# Power_Supply.net
KiCad netlist of a schematic drawn in Altium Designer
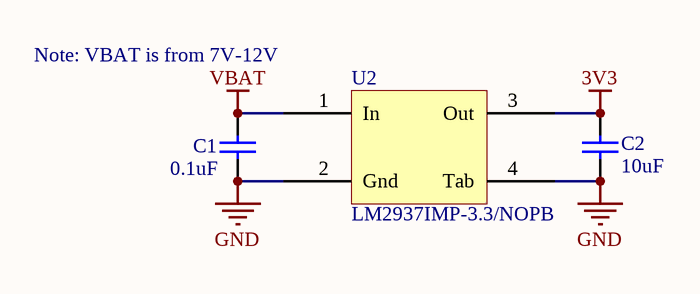
[diagram p0: Power Supply.SchDoc]

(export (version "E")
  (design (tool "Eeschema 10.0.6"))
  (components
    (comp (ref "C1")
      (value "0.1uF")
      (footprint "C1206")
      (description "Regulator Filter Cap")
      (fields (field (name "PUBLISHER") "Altium Limited"))
      (libsource (lib "Miscellaneous Devices") (part "Cap Semi"))
    )
    (comp (ref "C2")
      (value "10uF")
      (footprint "C1206")
      (description "1206 Ceramic Capacitor")
      (fields (field (name "PUBLISHER") "Altium Limited"))
      (libsource (lib "Miscellaneous Devices") (part "Cap Semi"))
    )
    (comp (ref "U2")
      (value "LM2937IMP-3.3/NOPB")
      (footprint "DSO-G3/C6.4")
      (libsource (lib "Speaker Library") (part "LM2937IMP-3.3/NOPB"))
    )
  )
  (nets
    (net (code "1") (name "3V3") (class "Default")
      (node (ref "C2") (pin "2") (pinfunction "2_2") (pintype "passive"))
      (node (ref "U2") (pin "3") (pinfunction "Out_3") (pintype "power_in"))
    )
    (net (code "2") (name "GND") (class "Default")
      (node (ref "C1") (pin "1") (pinfunction "1_1") (pintype "passive"))
      (node (ref "C2") (pin "1") (pinfunction "1_1") (pintype "passive"))
      (node (ref "U2") (pin "2") (pinfunction "Gnd_2") (pintype "power_in"))
      (node (ref "U2") (pin "4") (pinfunction "Tab_4") (pintype "power_in"))
    )
    (net (code "3") (name "VBAT") (class "Default")
      (node (ref "C1") (pin "2") (pinfunction "2_2") (pintype "passive"))
      (node (ref "U2") (pin "1") (pinfunction "In_1") (pintype "power_in"))
    )
  )
)
